# Sheet1.net
KiCad netlist of a schematic drawn in Altium Designer
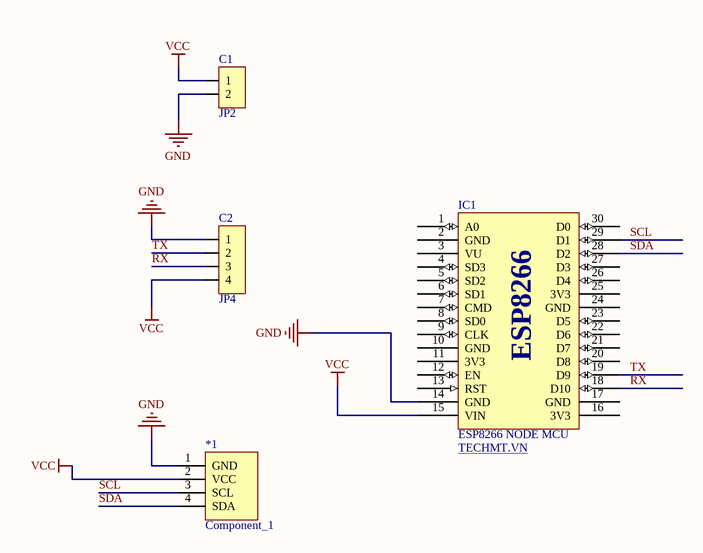
[diagram p0: Sheet1.SchDoc]

(export (version "E")
  (design (tool "Eeschema 10.0.6"))
  (components
    (comp (ref "*1")
      (value "Component_1")
      (footprint "oledi2c")
      (libsource (lib "oledi2c") (part "Component_1"))
    )
    (comp (ref "C1")
      (value "JP2")
      (footprint "JP2-C1T")
      (description "WR-PHD 2.54 mm Angled Socket Header")
      (fields
        (field (name "MANUFACTURER") "Würth Elektronik eiSos GmbH")
        (field (name "PARTNO") "613002143121")
        (field (name "CREATED BY") "Karrer Zheng")
      )
      (libsource (lib "TechMT.VN_Lib_Project v2") (part "JP2"))
    )
    (comp (ref "C2")
      (value "JP4")
      (footprint "JP4-C1T")
      (description "WR-PHD 2.54 mm Angled Socket Header")
      (fields
        (field (name "MANUFACTURER") "Würth Elektronik eiSos GmbH")
        (field (name "PARTNO") "613004143121")
        (field (name "CREATED BY") "Karrer Zheng")
      )
      (libsource (lib "TBV") (part "JP4"))
    )
    (comp (ref "IC1")
      (value "ESP8266 NODE MCU")
      (footprint "ESP8266 NodeMCU")
      (description "LUA-ESP8266 Wifi Module Techmt.vn")
      (fields (field (name "WEB") "TECHMT.VN"))
      (libsource (lib "TechMT.VN_Lib_Project v2") (part "ESP8266 NodeMCU"))
    )
  )
  (nets
    (net (code "1") (name "/RX") (class "Default")
      (node (ref "C2") (pin "3") (pinfunction "3_3") (pintype "passive"))
      (node (ref "IC1") (pin "18") (pinfunction "D10_18") (pintype "bidirectional"))
    )
    (net (code "2") (name "/SCL") (class "Default")
      (node (ref "*1") (pin "3") (pinfunction "SCL_3") (pintype "passive"))
      (node (ref "IC1") (pin "29") (pinfunction "D1_29") (pintype "bidirectional"))
    )
    (net (code "3") (name "/SDA") (class "Default")
      (node (ref "*1") (pin "4") (pinfunction "SDA_4") (pintype "passive"))
      (node (ref "IC1") (pin "28") (pinfunction "D2_28") (pintype "bidirectional"))
    )
    (net (code "4") (name "/TX") (class "Default")
      (node (ref "C2") (pin "2") (pinfunction "2_2") (pintype "passive"))
      (node (ref "IC1") (pin "19") (pinfunction "D9_19") (pintype "bidirectional"))
    )
    (net (code "5") (name "GND") (class "Default")
      (node (ref "*1") (pin "1") (pinfunction "GND_1") (pintype "passive"))
      (node (ref "C1") (pin "2") (pinfunction "2_2") (pintype "passive"))
      (node (ref "C2") (pin "1") (pinfunction "1_1") (pintype "passive"))
      (node (ref "IC1") (pin "14") (pinfunction "GND_14") (pintype "power_in"))
    )
    (net (code "6") (name "VCC") (class "Default")
      (node (ref "*1") (pin "2") (pinfunction "VCC_2") (pintype "passive"))
      (node (ref "C1") (pin "1") (pinfunction "1_1") (pintype "passive"))
      (node (ref "C2") (pin "4") (pinfunction "4_4") (pintype "passive"))
      (node (ref "IC1") (pin "15") (pinfunction "VIN_15") (pintype "power_in"))
    )
    (net (code "7") (name "unconnected-(IC1-3V3-Pad11)") (class "Default")
      (node (ref "IC1") (pin "11") (pinfunction "3V3_11") (pintype "power_in"))
    )
    (net (code "8") (name "unconnected-(IC1-3V3-Pad16)") (class "Default")
      (node (ref "IC1") (pin "16") (pinfunction "3V3_16") (pintype "power_in"))
    )
    (net (code "9") (name "unconnected-(IC1-3V3-Pad25)") (class "Default")
      (node (ref "IC1") (pin "25") (pinfunction "3V3_25") (pintype "power_in"))
    )
    (net (code "10") (name "unconnected-(IC1-A0-Pad1)") (class "Default")
      (node (ref "IC1") (pin "1") (pinfunction "A0_1") (pintype "bidirectional"))
    )
    (net (code "11") (name "unconnected-(IC1-CLK-Pad9)") (class "Default")
      (node (ref "IC1") (pin "9") (pinfunction "CLK_9") (pintype "bidirectional"))
    )
    (net (code "12") (name "unconnected-(IC1-CMD-Pad7)") (class "Default")
      (node (ref "IC1") (pin "7") (pinfunction "CMD_7") (pintype "bidirectional"))
    )
    (net (code "13") (name "unconnected-(IC1-D0-Pad30)") (class "Default")
      (node (ref "IC1") (pin "30") (pinfunction "D0_30") (pintype "bidirectional"))
    )
    (net (code "14") (name "unconnected-(IC1-D3-Pad27)") (class "Default")
      (node (ref "IC1") (pin "27") (pinfunction "D3_27") (pintype "bidirectional"))
    )
    (net (code "15") (name "unconnected-(IC1-D4-Pad26)") (class "Default")
      (node (ref "IC1") (pin "26") (pinfunction "D4_26") (pintype "bidirectional"))
    )
    (net (code "16") (name "unconnected-(IC1-D5-Pad23)") (class "Default")
      (node (ref "IC1") (pin "23") (pinfunction "D5_23") (pintype "bidirectional"))
    )
    (net (code "17") (name "unconnected-(IC1-D6-Pad22)") (class "Default")
      (node (ref "IC1") (pin "22") (pinfunction "D6_22") (pintype "bidirectional"))
    )
    (net (code "18") (name "unconnected-(IC1-D7-Pad21)") (class "Default")
      (node (ref "IC1") (pin "21") (pinfunction "D7_21") (pintype "bidirectional"))
    )
    (net (code "19") (name "unconnected-(IC1-D8-Pad20)") (class "Default")
      (node (ref "IC1") (pin "20") (pinfunction "D8_20") (pintype "bidirectional"))
    )
    (net (code "20") (name "unconnected-(IC1-EN-Pad12)") (class "Default")
      (node (ref "IC1") (pin "12") (pinfunction "EN_12") (pintype "bidirectional"))
    )
    (net (code "21") (name "unconnected-(IC1-GND-Pad2)") (class "Default")
      (node (ref "IC1") (pin "2") (pinfunction "GND_2") (pintype "power_in"))
    )
    (net (code "22") (name "unconnected-(IC1-GND-Pad10)") (class "Default")
      (node (ref "IC1") (pin "10") (pinfunction "GND_10") (pintype "power_in"))
    )
    (net (code "23") (name "unconnected-(IC1-GND-Pad17)") (class "Default")
      (node (ref "IC1") (pin "17") (pinfunction "GND_17") (pintype "power_in"))
    )
    (net (code "24") (name "unconnected-(IC1-GND-Pad24)") (class "Default")
      (node (ref "IC1") (pin "24") (pinfunction "GND_24") (pintype "power_in"))
    )
    (net (code "25") (name "unconnected-(IC1-RST-Pad13)") (class "Default")
      (node (ref "IC1") (pin "13") (pinfunction "RST_13") (pintype "input"))
    )
    (net (code "26") (name "unconnected-(IC1-SD0-Pad8)") (class "Default")
      (node (ref "IC1") (pin "8") (pinfunction "SD0_8") (pintype "bidirectional"))
    )
    (net (code "27") (name "unconnected-(IC1-SD1-Pad6)") (class "Default")
      (node (ref "IC1") (pin "6") (pinfunction "SD1_6") (pintype "bidirectional"))
    )
    (net (code "28") (name "unconnected-(IC1-SD2-Pad5)") (class "Default")
      (node (ref "IC1") (pin "5") (pinfunction "SD2_5") (pintype "bidirectional"))
    )
    (net (code "29") (name "unconnected-(IC1-SD3-Pad4)") (class "Default")
      (node (ref "IC1") (pin "4") (pinfunction "SD3_4") (pintype "bidirectional"))
    )
    (net (code "30") (name "unconnected-(IC1-VU-Pad3)") (class "Default")
      (node (ref "IC1") (pin "3") (pinfunction "VU_3") (pintype "power_in"))
    )
  )
)
